# LCD.net
KiCad netlist of a schematic drawn in Altium Designer
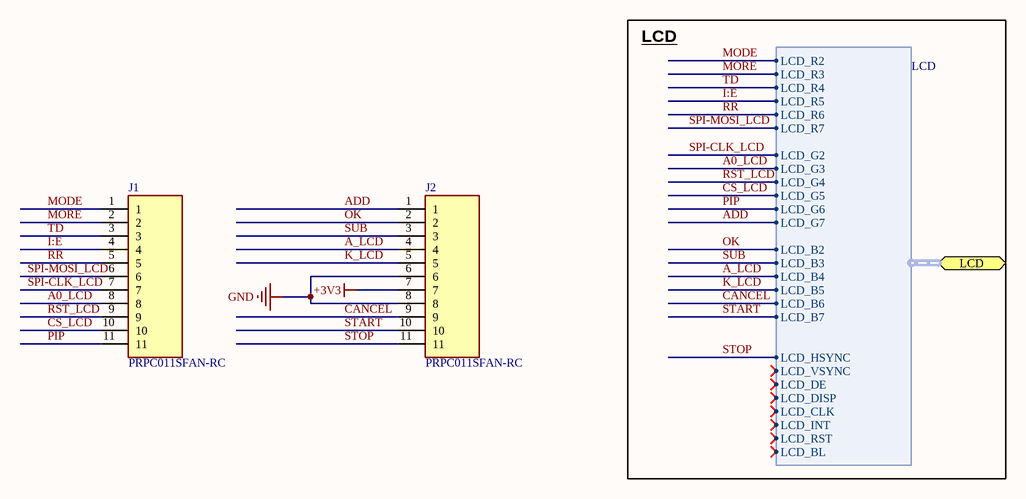
[diagram p0: LCD.SchDoc]

(export (version "E")
  (design (tool "Eeschema 10.0.6"))
  (components
    (comp (ref "J1")
      (value "PRPC011SFAN-RC")
      (footprint "1N4148")
      (description "Connector")
      (libsource (lib "*") (part "PRPC011SFAN-RC"))
    )
    (comp (ref "J2")
      (value "PRPC011SFAN-RC")
      (footprint "SamacSys:HDRV11W64P254_1X11_2794X254X1058P")
      (description "Connector")
      (libsource (lib "*") (part "PRPC011SFAN-RC"))
    )
  )
  (nets
    (net (code "2") (name "+3V3") (class "Default")
      (node (ref "J2") (pin "7") (pinfunction "7_7") (pintype "passive"))
    )
    (net (code "3") (name "/A0_LCD") (class "Default")
      (node (ref "J1") (pin "8") (pinfunction "8_8") (pintype "passive"))
    )
    (net (code "4") (name "/ADD") (class "Default")
      (node (ref "J2") (pin "1") (pinfunction "1_1") (pintype "passive"))
    )
    (net (code "5") (name "/A_LCD") (class "Default")
      (node (ref "J2") (pin "4") (pinfunction "4_4") (pintype "passive"))
    )
    (net (code "6") (name "/CANCEL") (class "Default")
      (node (ref "J2") (pin "9") (pinfunction "9_9") (pintype "passive"))
    )
    (net (code "7") (name "/CS_LCD") (class "Default")
      (node (ref "J1") (pin "10") (pinfunction "10_10") (pintype "passive"))
    )
    (net (code "8") (name "/I:E") (class "Default")
      (node (ref "J1") (pin "4") (pinfunction "4_4") (pintype "passive"))
    )
    (net (code "9") (name "/K_LCD") (class "Default")
      (node (ref "J2") (pin "5") (pinfunction "5_5") (pintype "passive"))
    )
    (net (code "10") (name "/MODE") (class "Default")
      (node (ref "J1") (pin "1") (pinfunction "1_1") (pintype "passive"))
    )
    (net (code "11") (name "/MORE") (class "Default")
      (node (ref "J1") (pin "2") (pinfunction "2_2") (pintype "passive"))
    )
    (net (code "12") (name "/OK") (class "Default")
      (node (ref "J2") (pin "2") (pinfunction "2_2") (pintype "passive"))
    )
    (net (code "13") (name "/PIP") (class "Default")
      (node (ref "J1") (pin "11") (pinfunction "11_11") (pintype "passive"))
    )
    (net (code "14") (name "/RR") (class "Default")
      (node (ref "J1") (pin "5") (pinfunction "5_5") (pintype "passive"))
    )
    (net (code "15") (name "/RST_LCD") (class "Default")
      (node (ref "J1") (pin "9") (pinfunction "9_9") (pintype "passive"))
    )
    (net (code "16") (name "/SPI-CLK_LCD") (class "Default")
      (node (ref "J1") (pin "7") (pinfunction "7_7") (pintype "passive"))
    )
    (net (code "17") (name "/SPI-MOSI_LCD") (class "Default")
      (node (ref "J1") (pin "6") (pinfunction "6_6") (pintype "passive"))
    )
    (net (code "18") (name "/START") (class "Default")
      (node (ref "J2") (pin "10") (pinfunction "10_10") (pintype "passive"))
    )
    (net (code "19") (name "/STOP") (class "Default")
      (node (ref "J2") (pin "11") (pinfunction "11_11") (pintype "passive"))
    )
    (net (code "20") (name "/SUB") (class "Default")
      (node (ref "J2") (pin "3") (pinfunction "3_3") (pintype "passive"))
    )
    (net (code "21") (name "/TD") (class "Default")
      (node (ref "J1") (pin "3") (pinfunction "3_3") (pintype "passive"))
    )
    (net (code "23") (name "GND") (class "Default")
      (node (ref "J2") (pin "6") (pinfunction "6_6") (pintype "passive"))
      (node (ref "J2") (pin "8") (pinfunction "8_8") (pintype "passive"))
    )
  )
)
